# Schematic.net
KiCad netlist of a schematic drawn in EAGLE
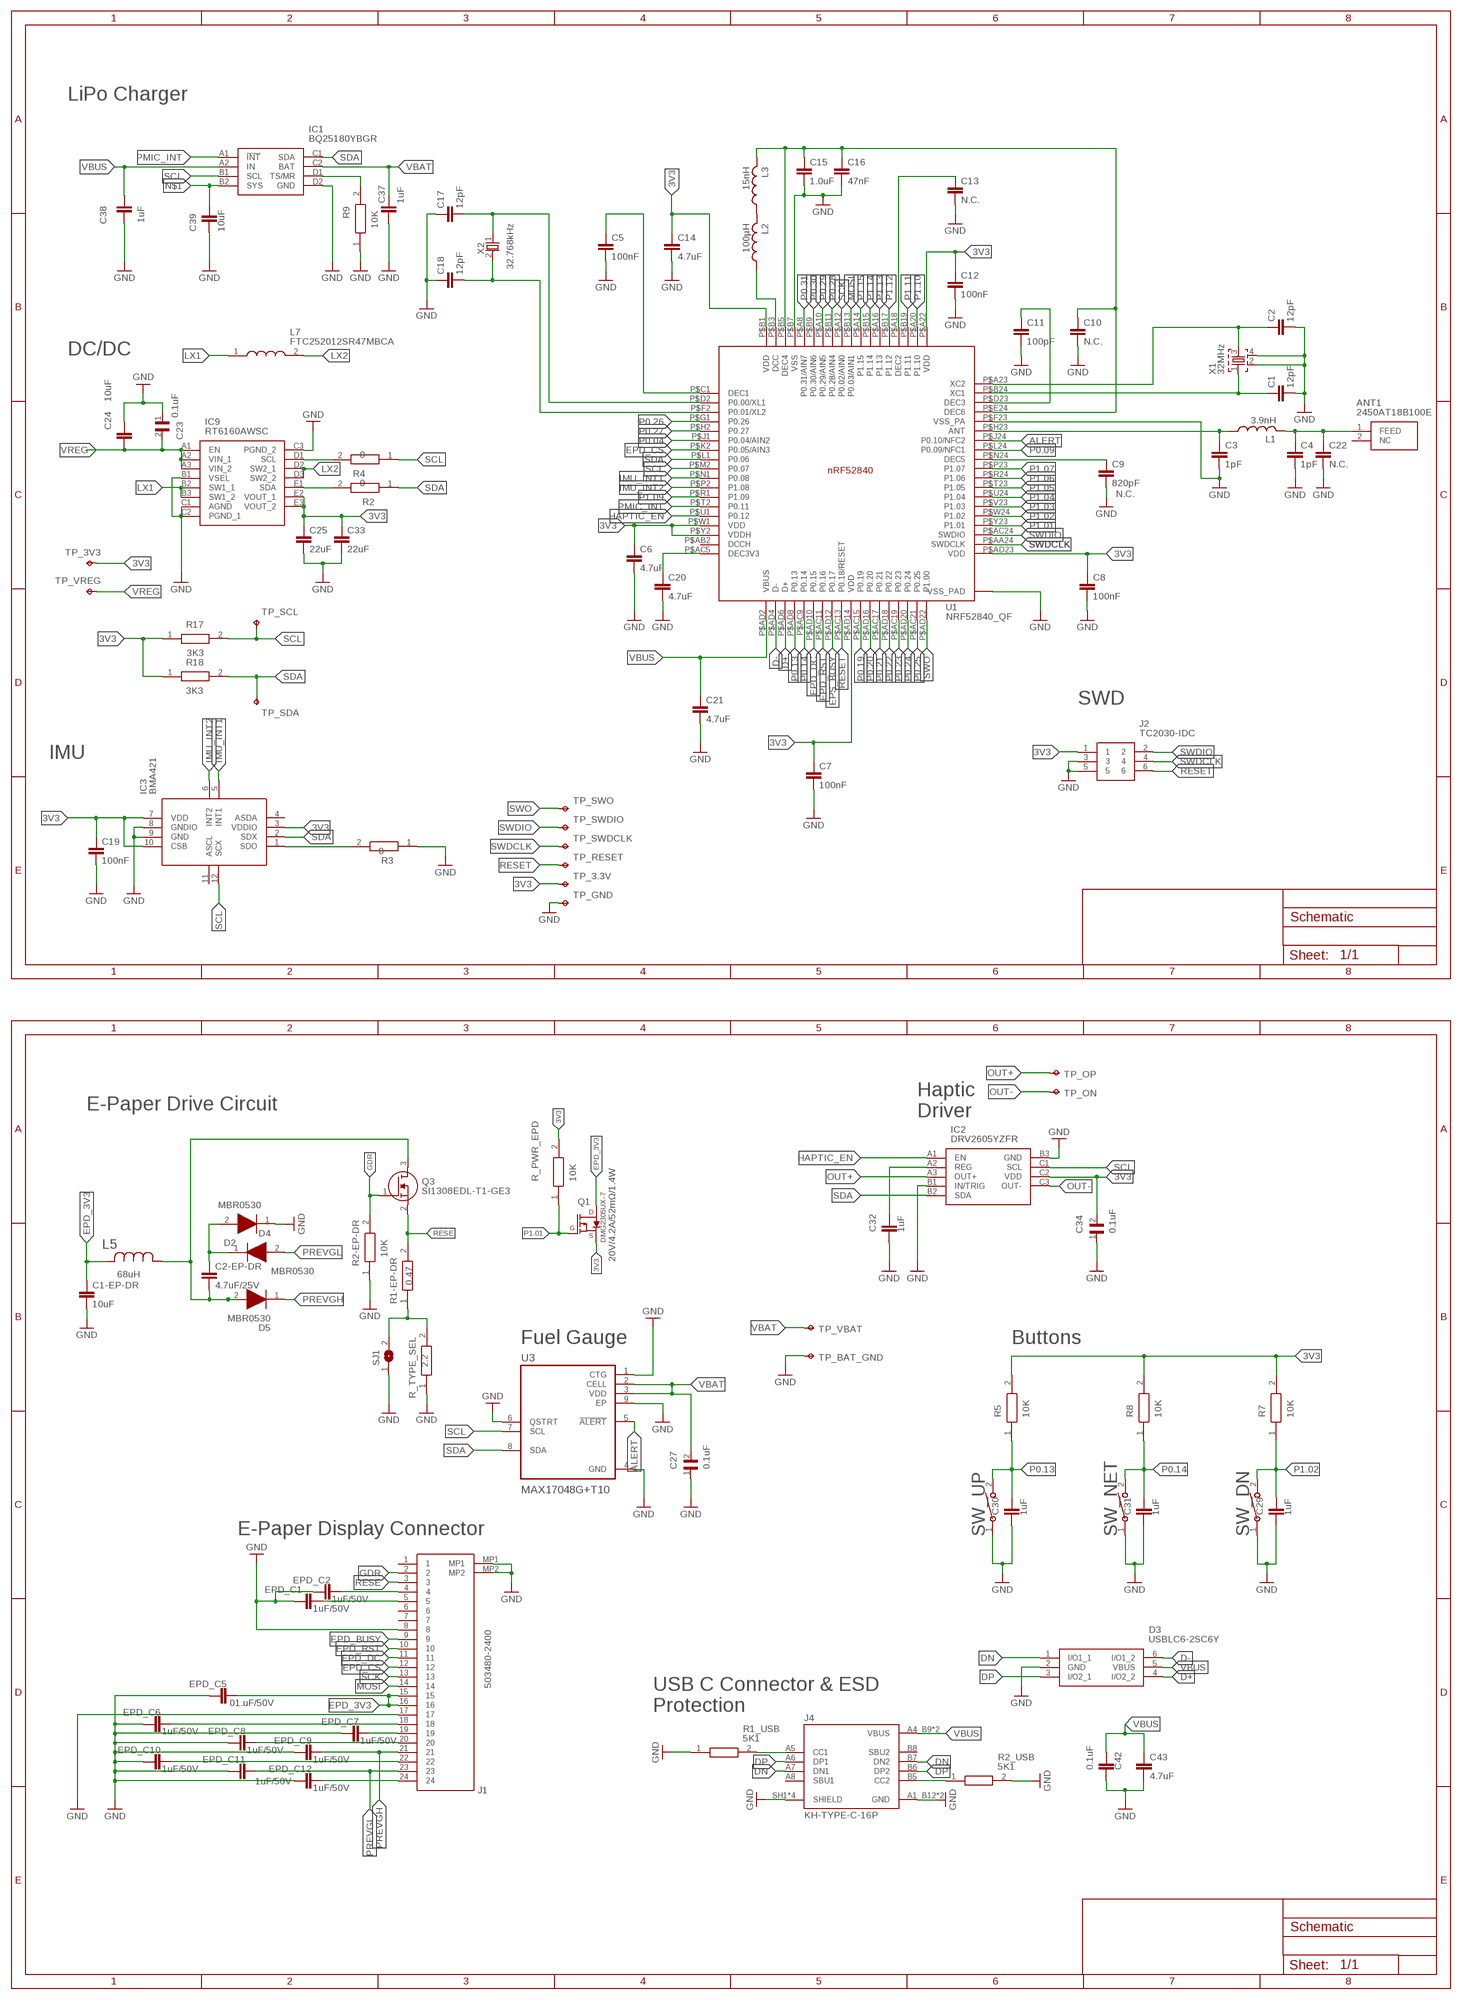
[diagram p0: schematic, sheet 1]

(export (version "E")
  (design (tool "Eeschema 10.0.6"))
  (components
    (comp (ref "ANT1")
      (value "2450AT18B100E")
      (footprint "eagle-import:2450AT18B100E_ANTC3216X140N")
      (fields (field (name "MOUSER_PART_NUMBER") "609-2450AT18B100E"))
      (libsource (lib "eagle-import") (part "2450AT18B100E_2450AT18B100E"))
    )
    (comp (ref "C1")
      (value "12pF")
      (footprint "eagle-import:NORDIC_NRF_3_RESC0201_L")
      (libsource (lib "eagle-import") (part "NORDIC_NRF_3_CAPACITOR_0201_L"))
    )
    (comp (ref "C1-EP-DR")
      (value "10uF")
      (footprint "eagle-import:NORDIC_NRF_3_RESC0201_L")
      (libsource (lib "eagle-import") (part "NORDIC_NRF_3_CAPACITOR_0201_L"))
    )
    (comp (ref "C2")
      (value "12pF")
      (footprint "eagle-import:NORDIC_NRF_3_RESC0201_L")
      (libsource (lib "eagle-import") (part "NORDIC_NRF_3_CAPACITOR_0201_L"))
    )
    (comp (ref "C2-EP-DR")
      (value "4.7uF/25V")
      (footprint "eagle-import:NORDIC_NRF_3_RESC0603_M")
      (libsource (lib "eagle-import") (part "NORDIC_NRF_3_CAPACITOR_0603_M"))
    )
    (comp (ref "C3")
      (value "1pF")
      (footprint "eagle-import:NORDIC_NRF_3_RESC0201_L")
      (libsource (lib "eagle-import") (part "NORDIC_NRF_3_CAPACITOR_0201_L"))
    )
    (comp (ref "C4")
      (value "1pF")
      (footprint "eagle-import:NORDIC_NRF_3_RESC0201_L")
      (libsource (lib "eagle-import") (part "NORDIC_NRF_3_CAPACITOR_0201_L"))
    )
    (comp (ref "C5")
      (value "100nF")
      (footprint "eagle-import:NORDIC_NRF_3_RESC0201_L")
      (libsource (lib "eagle-import") (part "NORDIC_NRF_3_CAPACITOR_0201_L"))
    )
    (comp (ref "C6")
      (value "4.7uF")
      (footprint "eagle-import:NORDIC_NRF_3_RESC0402_M")
      (libsource (lib "eagle-import") (part "NORDIC_NRF_3_CAPACITOR_0402_M"))
    )
    (comp (ref "C7")
      (value "100nF")
      (footprint "eagle-import:NORDIC_NRF_3_RESC0201_L")
      (libsource (lib "eagle-import") (part "NORDIC_NRF_3_CAPACITOR_0201_L"))
    )
    (comp (ref "C8")
      (value "100nF")
      (footprint "eagle-import:NORDIC_NRF_3_RESC0201_L")
      (libsource (lib "eagle-import") (part "NORDIC_NRF_3_CAPACITOR_0201_L"))
    )
    (comp (ref "C9")
      (value "820pF")
      (footprint "eagle-import:NORDIC_NRF_3_RESC0201_L")
      (fields (field (name "MAXTEMP") "N.C."))
      (libsource (lib "eagle-import") (part "NORDIC_NRF_3_CAPACITOR_0201_L"))
    )
    (comp (ref "C10")
      (value "N.C.")
      (footprint "eagle-import:NORDIC_NRF_3_RESC0201_L")
      (libsource (lib "eagle-import") (part "NORDIC_NRF_3_CAPACITOR_0201_L"))
    )
    (comp (ref "C11")
      (value "100pF")
      (footprint "eagle-import:NORDIC_NRF_3_RESC0201_L")
      (libsource (lib "eagle-import") (part "NORDIC_NRF_3_CAPACITOR_0201_L"))
    )
    (comp (ref "C12")
      (value "100nF")
      (footprint "eagle-import:NORDIC_NRF_3_RESC0201_L")
      (libsource (lib "eagle-import") (part "NORDIC_NRF_3_CAPACITOR_0201_L"))
    )
    (comp (ref "C13")
      (value "N.C.")
      (footprint "eagle-import:NORDIC_NRF_3_RESC0201_L")
      (libsource (lib "eagle-import") (part "NORDIC_NRF_3_CAPACITOR_0201_L"))
    )
    (comp (ref "C14")
      (value "4.7uF")
      (footprint "eagle-import:NORDIC_NRF_3_RESC0402_M")
      (libsource (lib "eagle-import") (part "NORDIC_NRF_3_CAPACITOR_0402_M"))
    )
    (comp (ref "C15")
      (value "1.0uF")
      (footprint "eagle-import:NORDIC_NRF_3_RESC0402_M")
      (libsource (lib "eagle-import") (part "NORDIC_NRF_3_CAPACITOR_0402_M"))
    )
    (comp (ref "C16")
      (value "47nF")
      (footprint "eagle-import:NORDIC_NRF_3_RESC0201_L")
      (libsource (lib "eagle-import") (part "NORDIC_NRF_3_CAPACITOR_0201_L"))
    )
    (comp (ref "C17")
      (value "12pF")
      (footprint "eagle-import:NORDIC_NRF_3_RESC0201_L")
      (libsource (lib "eagle-import") (part "NORDIC_NRF_3_CAPACITOR_0201_L"))
    )
    (comp (ref "C18")
      (value "12pF")
      (footprint "eagle-import:NORDIC_NRF_3_RESC0201_L")
      (libsource (lib "eagle-import") (part "NORDIC_NRF_3_CAPACITOR_0201_L"))
    )
    (comp (ref "C19")
      (value "100nF")
      (footprint "eagle-import:NORDIC_NRF_3_RESC0201_L")
      (libsource (lib "eagle-import") (part "NORDIC_NRF_3_CAPACITOR_0201_L"))
    )
    (comp (ref "C20")
      (value "4.7uF")
      (footprint "eagle-import:NORDIC_NRF_3_RESC0402_M")
      (libsource (lib "eagle-import") (part "NORDIC_NRF_3_CAPACITOR_0402_M"))
    )
    (comp (ref "C21")
      (value "4.7uF")
      (footprint "eagle-import:NORDIC_NRF_3_RESC0402_M")
      (libsource (lib "eagle-import") (part "NORDIC_NRF_3_CAPACITOR_0402_M"))
    )
    (comp (ref "C22")
      (value "N.C.")
      (footprint "eagle-import:NORDIC_NRF_3_RESC0201_L")
      (libsource (lib "eagle-import") (part "NORDIC_NRF_3_CAPACITOR_0201_L"))
    )
    (comp (ref "C23")
      (value "0.1uF")
      (footprint "eagle-import:GRM011R60J152KE01L_2_CAPC0201X13N")
      (fields (field (name "MF") "Murata") (field (name "MP") "GRM011R60J152KE01L"))
      (libsource (lib "eagle-import") (part "GRM011R60J152KE01L_2_GRM011R60J152KE01L"))
    )
    (comp (ref "C24")
      (value "10uF")
      (footprint "eagle-import:NORDIC_NRF_3_RESC0402_M")
      (libsource (lib "eagle-import") (part "NORDIC_NRF_3_CAPACITOR_0402_M"))
    )
    (comp (ref "C25")
      (value "22uF")
      (footprint "eagle-import:NORDIC_NRF_3_RESC0402_M")
      (libsource (lib "eagle-import") (part "NORDIC_NRF_3_CAPACITOR_0402_M"))
    )
    (comp (ref "C27")
      (value "0.1uF")
      (footprint "eagle-import:GRM011R60J152KE01L_2_CAPC0201X13N")
      (fields (field (name "MF") "Murata") (field (name "MP") "GRM011R60J152KE01L"))
      (libsource (lib "eagle-import") (part "GRM011R60J152KE01L_2_GRM011R60J152KE01L"))
    )
    (comp (ref "C29")
      (value "1uF")
      (footprint "eagle-import:NORDIC_NRF_3_RESC0402_M")
      (libsource (lib "eagle-import") (part "NORDIC_NRF_3_CAPACITOR_0402_M"))
    )
    (comp (ref "C30")
      (value "1uF")
      (footprint "eagle-import:NORDIC_NRF_3_RESC0402_M")
      (libsource (lib "eagle-import") (part "NORDIC_NRF_3_CAPACITOR_0402_M"))
    )
    (comp (ref "C31")
      (value "1uF")
      (footprint "eagle-import:NORDIC_NRF_3_RESC0402_M")
      (libsource (lib "eagle-import") (part "NORDIC_NRF_3_CAPACITOR_0402_M"))
    )
    (comp (ref "C32")
      (value "1uF")
      (footprint "eagle-import:NORDIC_NRF_3_RESC0402_M")
      (libsource (lib "eagle-import") (part "NORDIC_NRF_3_CAPACITOR_0402_M"))
    )
    (comp (ref "C33")
      (value "22uF")
      (footprint "eagle-import:NORDIC_NRF_3_RESC0402_M")
      (libsource (lib "eagle-import") (part "NORDIC_NRF_3_CAPACITOR_0402_M"))
    )
    (comp (ref "C34")
      (value "0.1uF")
      (footprint "eagle-import:GRM011R60J152KE01L_2_CAPC0201X13N")
      (fields (field (name "MF") "Murata") (field (name "MP") "GRM011R60J152KE01L"))
      (libsource (lib "eagle-import") (part "GRM011R60J152KE01L_2_GRM011R60J152KE01L"))
    )
    (comp (ref "C37")
      (value "1uF")
      (footprint "eagle-import:NORDIC_NRF_3_RESC0402_M")
      (libsource (lib "eagle-import") (part "NORDIC_NRF_3_CAPACITOR_0402_M"))
    )
    (comp (ref "C38")
      (value "1uF")
      (footprint "eagle-import:NORDIC_NRF_3_RESC0402_L")
      (libsource (lib "eagle-import") (part "NORDIC_NRF_3_CAPACITOR_0402_L"))
    )
    (comp (ref "C39")
      (value "10uF")
      (footprint "eagle-import:NORDIC_NRF_3_RESC0402_N")
      (libsource (lib "eagle-import") (part "NORDIC_NRF_3_CAPACITOR_0402_N"))
    )
    (comp (ref "C42")
      (value "0.1uF")
      (footprint "eagle-import:NORDIC_NRF_3_RESC0201_L")
      (libsource (lib "eagle-import") (part "NORDIC_NRF_3_CAPACITOR_0201_L"))
    )
    (comp (ref "C43")
      (value "4.7uF")
      (footprint "eagle-import:NORDIC_NRF_3_RESC0402_M")
      (libsource (lib "eagle-import") (part "NORDIC_NRF_3_CAPACITOR_0402_M"))
    )
    (comp (ref "D2")
      (value "MBR0530")
      (footprint "eagle-import:ESP32_C6_LIBRARY_5_SOD3716X135N")
      (fields (field (name "MF") "ON Semiconductor"))
      (libsource (lib "eagle-import") (part "ESP32_C6_LIBRARY_5_MBR0530"))
    )
    (comp (ref "D3")
      (value "USBLC6-2SC6Y")
      (footprint "eagle-import:ESP32_C6_LIBRARY_3_SOT95P280X145-6N")
      (fields (field (name "MF") "STMicroelectronics"))
      (libsource (lib "eagle-import") (part "ESP32_C6_LIBRARY_3_USBLC6-2SC6Y"))
    )
    (comp (ref "D4")
      (value "MBR0530")
      (footprint "eagle-import:ESP32_C6_LIBRARY_5_SOD3716X135N")
      (fields (field (name "MF") "ON Semiconductor"))
      (libsource (lib "eagle-import") (part "ESP32_C6_LIBRARY_5_MBR0530"))
    )
    (comp (ref "D5")
      (value "MBR0530")
      (footprint "eagle-import:ESP32_C6_LIBRARY_5_SOD3716X135N")
      (fields (field (name "MF") "ON Semiconductor"))
      (libsource (lib "eagle-import") (part "ESP32_C6_LIBRARY_5_MBR0530"))
    )
    (comp (ref "EPD_C1")
      (value "1uF/50V")
      (footprint "eagle-import:NORDIC_NRF_3_RESC0603_M")
      (libsource (lib "eagle-import") (part "NORDIC_NRF_3_CAPACITOR_0603_M"))
    )
    (comp (ref "EPD_C2")
      (value "1uF/50V")
      (footprint "eagle-import:NORDIC_NRF_3_RESC0603_M")
      (libsource (lib "eagle-import") (part "NORDIC_NRF_3_CAPACITOR_0603_M"))
    )
    (comp (ref "EPD_C5")
      (value "01.uF/50V")
      (footprint "eagle-import:NORDIC_NRF_3_RESC0603_M")
      (libsource (lib "eagle-import") (part "NORDIC_NRF_3_CAPACITOR_0603_M"))
    )
    (comp (ref "EPD_C6")
      (value "1uF/50V")
      (footprint "eagle-import:NORDIC_NRF_3_RESC0603_M")
      (libsource (lib "eagle-import") (part "NORDIC_NRF_3_CAPACITOR_0603_M"))
    )
    (comp (ref "EPD_C7")
      (value "1uF/50V")
      (footprint "eagle-import:NORDIC_NRF_3_RESC0603_M")
      (libsource (lib "eagle-import") (part "NORDIC_NRF_3_CAPACITOR_0603_M"))
    )
    (comp (ref "EPD_C8")
      (value "1uF/50V")
      (footprint "eagle-import:NORDIC_NRF_3_RESC0603_M")
      (libsource (lib "eagle-import") (part "NORDIC_NRF_3_CAPACITOR_0603_M"))
    )
    (comp (ref "EPD_C9")
      (value "1uF/50V")
      (footprint "eagle-import:NORDIC_NRF_3_RESC0603_M")
      (libsource (lib "eagle-import") (part "NORDIC_NRF_3_CAPACITOR_0603_M"))
    )
    (comp (ref "EPD_C10")
      (value "1uF/50V")
      (footprint "eagle-import:NORDIC_NRF_3_RESC0603_M")
      (libsource (lib "eagle-import") (part "NORDIC_NRF_3_CAPACITOR_0603_M"))
    )
    (comp (ref "EPD_C11")
      (value "1uF/50V")
      (footprint "eagle-import:NORDIC_NRF_3_RESC0603_M")
      (libsource (lib "eagle-import") (part "NORDIC_NRF_3_CAPACITOR_0603_M"))
    )
    (comp (ref "EPD_C12")
      (value "1uF/50V")
      (footprint "eagle-import:NORDIC_NRF_3_RESC0603_M")
      (libsource (lib "eagle-import") (part "NORDIC_NRF_3_CAPACITOR_0603_M"))
    )
    (comp (ref "IC1")
      (value "BQ25180YBGR")
      (footprint "eagle-import:BQ25180YBGR_BGA8C40P2X4_100X155X50")
      (fields (field (name "MOUSER_PART_NUMBER") "595-BQ25180YBGR"))
      (libsource (lib "eagle-import") (part "BQ25180YBGR_BQ25180YBGR"))
    )
    (comp (ref "IC2")
      (value "DRV2605YZFR")
      (footprint "eagle-import:DRV2605YZFR_BGA9C50P3X3_144X144X62")
      (libsource (lib "eagle-import") (part "DRV2605YZFR_DRV2605YZFR"))
    )
    (comp (ref "IC3")
      (value "BMA421")
      (footprint "eagle-import:BMA423_BMA423")
      (fields (field (name "ARROW_PART_NUMBER") "BMA423") (field (name "MOUSER_PART_NUMBER") "262-BMA423"))
      (libsource (lib "eagle-import") (part "BMA423_BMA423"))
    )
    (comp (ref "IC9")
      (value "RT6160AWSC")
      (footprint "eagle-import:RT6160AWSC_BGA15C40P3X5_140X230X60")
      (fields (field (name "MOUSER_PART_NUMBER") "835-RT6160AWSC"))
      (libsource (lib "eagle-import") (part "RT6160AWSC_RT6160AWSC"))
    )
    (comp (ref "J1")
      (value "503480-2400")
      (footprint "eagle-import:503480-2400_5034802400")
      (fields (field (name "MOUSER_PART_NUMBER") "538-503480-2400"))
      (libsource (lib "eagle-import") (part "503480-2400_503480-2400"))
    )
    (comp (ref "J2")
      (value "TC2030-IDC")
      (footprint "eagle-import:TC2030-IDC_TC2030IDC")
      (libsource (lib "eagle-import") (part "TC2030-IDC_TC2030-IDC"))
    )
    (comp (ref "J4")
      (value "KH-TYPE-C-16P")
      (footprint "eagle-import:KH-TYPE-C-16P_KINGHELM_KH-TYPE-C-16P")
      (fields (field (name "MF") "kinghelm"))
      (libsource (lib "eagle-import") (part "KH-TYPE-C-16P_KH-TYPE-C-16P"))
    )
    (comp (ref "L1")
      (value "3.9nH")
      (footprint "eagle-import:NORDIC_NRF_2_RESC0402_L")
      (libsource (lib "eagle-import") (part "NORDIC_NRF_2_INDUCTOR_0402_L"))
    )
    (comp (ref "L2")
      (value "100µH")
      (footprint "eagle-import:NORDIC_NRF_2_RESC0402_L")
      (libsource (lib "eagle-import") (part "NORDIC_NRF_2_INDUCTOR_0402_L"))
    )
    (comp (ref "L3")
      (value "15nH")
      (footprint "eagle-import:NORDIC_NRF_2_RESC0402_L")
      (libsource (lib "eagle-import") (part "NORDIC_NRF_2_INDUCTOR_0402_L"))
    )
    (comp (ref "L5")
      (value "68uH")
      (footprint "eagle-import:ESP32_C6_LIBRARY_2_IND_4828-WE-TPC_WRE")
      (fields
        (field (name "MANUFACTURER_PART_NUMBER") "744043680")
        (field (name "COPYRIGHT") "Copyright (C) 2024 Ultra Librarian. All rights reserved.")
      )
      (libsource (lib "eagle-import") (part "ESP32_C6_LIBRARY_2_744043680IND_4828-WE-TPC_WRE"))
    )
    (comp (ref "L7")
      (value "FTC252012SR47MBCA")
      (footprint "eagle-import:MLP2016SR47MT0S1_INDC2016X100N")
      (libsource (lib "eagle-import") (part "MLP2016SR47MT0S1_FTC252012SR47MBCA"))
    )
    (comp (ref "Q1")
      (value "20V/4.2A/52mΩ/1.4W")
      (footprint "eagle-import:ESP32_C6_LIBRARY_4_ESP32_C6_LIBRARY_4_ESP32_C6_LIBRARY_4_ESP32_C6_LIBRARY_4_ESP32_WROVER_SPARKFUN-DISCRETESEMI_SOT23-3")
      (libsource (lib "eagle-import") (part "ESP32_C6_LIBRARY_4_ESP32_WROVER_SPARKFUN-DISCRETESEMI_MOSFET_PCH-DMG2305UX-7"))
    )
    (comp (ref "Q3")
      (value "SI1308EDL-T1-GE3")
      (footprint "eagle-import:ESP32_C6_LIBRARY_6_SOT65P210X110-3N")
      (fields (field (name "MF") "Vishay Siliconix"))
      (libsource (lib "eagle-import") (part "ESP32_C6_LIBRARY_6_SI1308EDL-T1-GE3"))
    )
    (comp (ref "R1-EP-DR")
      (value "0.47")
      (footprint "eagle-import:ERA-1AEB3401C_0201")
      (libsource (lib "eagle-import") (part "ERA-1AEB3401C_CPF0201D7K68C1"))
    )
    (comp (ref "R1_USB")
      (value "5K1")
      (footprint "eagle-import:ERA-1AEB3401C_0201")
      (libsource (lib "eagle-import") (part "ERA-1AEB3401C_CPF0201D7K68C1"))
    )
    (comp (ref "R2")
      (value "0")
      (footprint "eagle-import:ERA-1AEB3401C_0201")
      (libsource (lib "eagle-import") (part "ERA-1AEB3401C_CPF0201D7K68C1"))
    )
    (comp (ref "R2-EP-DR")
      (value "10K")
      (footprint "eagle-import:ERA-1AEB3401C_0201")
      (libsource (lib "eagle-import") (part "ERA-1AEB3401C_CPF0201D7K68C1"))
    )
    (comp (ref "R2_USB")
      (value "5K1")
      (footprint "eagle-import:ERA-1AEB3401C_0201")
      (libsource (lib "eagle-import") (part "ERA-1AEB3401C_CPF0201D7K68C1"))
    )
    (comp (ref "R3")
      (value "0")
      (footprint "eagle-import:ERA-1AEB3401C_0201")
      (libsource (lib "eagle-import") (part "ERA-1AEB3401C_CPF0201D7K68C1"))
    )
    (comp (ref "R4")
      (value "0")
      (footprint "eagle-import:ERA-1AEB3401C_0201")
      (libsource (lib "eagle-import") (part "ERA-1AEB3401C_CPF0201D7K68C1"))
    )
    (comp (ref "R5")
      (value "10K")
      (footprint "eagle-import:ERA-1AEB3401C_0201")
      (libsource (lib "eagle-import") (part "ERA-1AEB3401C_CPF0201D7K68C1"))
    )
    (comp (ref "R7")
      (value "10K")
      (footprint "eagle-import:ERA-1AEB3401C_0201")
      (libsource (lib "eagle-import") (part "ERA-1AEB3401C_CPF0201D7K68C1"))
    )
    (comp (ref "R8")
      (value "10K")
      (footprint "eagle-import:ERA-1AEB3401C_0201")
      (libsource (lib "eagle-import") (part "ERA-1AEB3401C_CPF0201D7K68C1"))
    )
    (comp (ref "R9")
      (value "10K")
      (footprint "eagle-import:ERA-1AEB3401C_0201")
      (libsource (lib "eagle-import") (part "ERA-1AEB3401C_CPF0201D7K68C1"))
    )
    (comp (ref "R17")
      (value "3K3")
      (footprint "eagle-import:ERA-1AEB3401C_0201")
      (libsource (lib "eagle-import") (part "ERA-1AEB3401C_CPF0201D7K68C1"))
    )
    (comp (ref "R18")
      (value "3K3")
      (footprint "eagle-import:ERA-1AEB3401C_0201")
      (libsource (lib "eagle-import") (part "ERA-1AEB3401C_CPF0201D7K68C1"))
    )
    (comp (ref "R_PWR_EPD")
      (value "10K")
      (footprint "eagle-import:ERA-1AEB3401C_0201")
      (libsource (lib "eagle-import") (part "ERA-1AEB3401C_CPF0201D7K68C1"))
    )
    (comp (ref "R_TYPE_SEL")
      (value "2.2")
      (footprint "eagle-import:ERA-1AEB3401C_0201")
      (libsource (lib "eagle-import") (part "ERA-1AEB3401C_CPF0201D7K68C1"))
    )
    (comp (ref "SJ1")
      (value "ESP32_C6_LIBRARY_7_JUMPER_SJ")
      (footprint "eagle-import:ESP32_C6_LIBRARY_7_JUMPER_SJ")
      (libsource (lib "eagle-import") (part "ESP32_C6_LIBRARY_7_JUMPER_SJ"))
    )
    (comp (ref "SW_DN")
      (value "2025-10-22_07-23-44_LIBRARY_EVP-AKE31ASW_EVP-AKE31A_PAN")
      (footprint "eagle-import:2025-10-22_07-23-44_LIBRARY_SW_EVP-AKE31A_PAN")
      (fields
        (field (name "MANUFACTURER_PART_NUMBER") "EVP-AKE31A")
        (field (name "COPYRIGHT") "Copyright (C) 2025 Ultra Librarian. All rights reserved.")
      )
      (libsource (lib "eagle-import") (part "2025-10-22_07-23-44_LIBRARY_EVP-AKE31ASW_EVP-AKE31A_PAN"))
    )
    (comp (ref "SW_NET")
      (value "2025-10-22_07-23-44_LIBRARY_EVP-AKE31ASW_EVP-AKE31A_PAN")
      (footprint "eagle-import:2025-10-22_07-23-44_LIBRARY_SW_EVP-AKE31A_PAN")
      (fields
        (field (name "MANUFACTURER_PART_NUMBER") "EVP-AKE31A")
        (field (name "COPYRIGHT") "Copyright (C) 2025 Ultra Librarian. All rights reserved.")
      )
      (libsource (lib "eagle-import") (part "2025-10-22_07-23-44_LIBRARY_EVP-AKE31ASW_EVP-AKE31A_PAN"))
    )
    (comp (ref "SW_UP")
      (value "2025-10-22_07-23-44_LIBRARY_EVP-AKE31ASW_EVP-AKE31A_PAN")
      (footprint "eagle-import:2025-10-22_07-23-44_LIBRARY_SW_EVP-AKE31A_PAN")
      (fields
        (field (name "MANUFACTURER_PART_NUMBER") "EVP-AKE31A")
        (field (name "COPYRIGHT") "Copyright (C) 2025 Ultra Librarian. All rights reserved.")
      )
      (libsource (lib "eagle-import") (part "2025-10-22_07-23-44_LIBRARY_EVP-AKE31ASW_EVP-AKE31A_PAN"))
    )
    (comp (ref "TP_3.3V")
      (value "HECTOR_WATCH_1_TPTP20R")
      (footprint "eagle-import:HECTOR_WATCH_1_TP20R")
      (libsource (lib "eagle-import") (part "HECTOR_WATCH_1_TPTP20R"))
    )
    (comp (ref "TP_3V3")
      (value "HECTOR_WATCH_1_TPTP20R")
      (footprint "eagle-import:HECTOR_WATCH_1_TP20R")
      (libsource (lib "eagle-import") (part "HECTOR_WATCH_1_TPTP20R"))
    )
    (comp (ref "TP_BAT_GND")
      (value "HECTOR_WATCH_1_TPTP20R")
      (footprint "eagle-import:HECTOR_WATCH_1_TP20R")
      (libsource (lib "eagle-import") (part "HECTOR_WATCH_1_TPTP20R"))
    )
    (comp (ref "TP_GND")
      (value "HECTOR_WATCH_1_TPTP20R")
      (footprint "eagle-import:HECTOR_WATCH_1_TP20R")
      (libsource (lib "eagle-import") (part "HECTOR_WATCH_1_TPTP20R"))
    )
    (comp (ref "TP_ON")
      (value "HECTOR_WATCH_1_TPTP20R")
      (footprint "eagle-import:HECTOR_WATCH_1_TP20R")
      (libsource (lib "eagle-import") (part "HECTOR_WATCH_1_TPTP20R"))
    )
    (comp (ref "TP_OP")
      (value "HECTOR_WATCH_1_TPTP20R")
      (footprint "eagle-import:HECTOR_WATCH_1_TP20R")
      (libsource (lib "eagle-import") (part "HECTOR_WATCH_1_TPTP20R"))
    )
    (comp (ref "TP_RESET")
      (value "HECTOR_WATCH_1_TPTP20R")
      (footprint "eagle-import:HECTOR_WATCH_1_TP20R")
      (libsource (lib "eagle-import") (part "HECTOR_WATCH_1_TPTP20R"))
    )
    (comp (ref "TP_SCL")
      (value "HECTOR_WATCH_1_TPTP20R")
      (footprint "eagle-import:HECTOR_WATCH_1_TP20R")
      (libsource (lib "eagle-import") (part "HECTOR_WATCH_1_TPTP20R"))
    )
    (comp (ref "TP_SDA")
      (value "HECTOR_WATCH_1_TPTP20R")
      (footprint "eagle-import:HECTOR_WATCH_1_TP20R")
      (libsource (lib "eagle-import") (part "HECTOR_WATCH_1_TPTP20R"))
    )
    (comp (ref "TP_SWDCLK")
      (value "HECTOR_WATCH_1_TPTP20R")
      (footprint "eagle-import:HECTOR_WATCH_1_TP20R")
      (libsource (lib "eagle-import") (part "HECTOR_WATCH_1_TPTP20R"))
    )
    (comp (ref "TP_SWDIO")
      (value "HECTOR_WATCH_1_TPTP20R")
      (footprint "eagle-import:HECTOR_WATCH_1_TP20R")
      (libsource (lib "eagle-import") (part "HECTOR_WATCH_1_TPTP20R"))
    )
    (comp (ref "TP_SWO")
      (value "HECTOR_WATCH_1_TPTP20R")
      (footprint "eagle-import:HECTOR_WATCH_1_TP20R")
      (libsource (lib "eagle-import") (part "HECTOR_WATCH_1_TPTP20R"))
    )
    (comp (ref "TP_VBAT")
      (value "HECTOR_WATCH_1_TPTP20R")
      (footprint "eagle-import:HECTOR_WATCH_1_TP20R")
      (libsource (lib "eagle-import") (part "HECTOR_WATCH_1_TPTP20R"))
    )
    (comp (ref "TP_VREG")
      (value "HECTOR_WATCH_1_TPTP20R")
      (footprint "eagle-import:HECTOR_WATCH_1_TP20R")
      (libsource (lib "eagle-import") (part "HECTOR_WATCH_1_TPTP20R"))
    )
    (comp (ref "U1")
      (value "NRF52840_QF")
      (footprint "eagle-import:NORDIC_NRF_4_AQFN50P700X700X85_HS-74N")
      (libsource (lib "eagle-import") (part "NORDIC_NRF_4_NRF52840_QF"))
    )
    (comp (ref "U3")
      (value "MAX17048G+T10")
      (footprint "eagle-import:ESP32_C6_LIBRARY_SON50P200X200X80-9N")
      (fields (field (name "MF") "Analog Devices"))
      (libsource (lib "eagle-import") (part "ESP32_C6_LIBRARY_MAX17048G+T10"))
    )
    (comp (ref "X1")
      (value "32MHz")
      (footprint "eagle-import:NORDIC_NRF_BT-XTAL_2016_N")
      (libsource (lib "eagle-import") (part "NORDIC_NRF_XTAL_32MHZ"))
    )
    (comp (ref "X2")
      (value "32.768kHz")
      (footprint "eagle-import:NORDIC_NRF_1_XTAL_3215_N")
      (libsource (lib "eagle-import") (part "NORDIC_NRF_1_XTAL_32KHZ"))
    )
  )
  (nets
    (net (code "1") (name "3V3") (class "Default")
      (node (ref "C12") (pin "1") (pinfunction "1_1") (pintype "passive"))
      (node (ref "C14") (pin "1") (pinfunction "1_1") (pintype "passive"))
      (node (ref "C19") (pin "1") (pinfunction "1_1") (pintype "passive"))
      (node (ref "C25") (pin "1") (pinfunction "1_1") (pintype "passive"))
      (node (ref "C33") (pin "1") (pinfunction "1_1") (pintype "passive"))
      (node (ref "C34") (pin "2") (pinfunction "2_2") (pintype "passive"))
      (node (ref "C6") (pin "1") (pinfunction "1_1") (pintype "passive"))
      (node (ref "C7") (pin "1") (pinfunction "1_1") (pintype "passive"))
      (node (ref "C8") (pin "1") (pinfunction "1_1") (pintype "passive"))
      (node (ref "IC2") (pin "C2") (pinfunction "VDD_C2") (pintype "bidirectional"))
      (node (ref "IC3") (pin "10") (pinfunction "CSB_10") (pintype "bidirectional"))
      (node (ref "IC3") (pin "3") (pinfunction "VDDIO_3") (pintype "bidirectional"))
      (node (ref "IC3") (pin "7") (pinfunction "VDD_7") (pintype "bidirectional"))
      (node (ref "IC9") (pin "E2") (pinfunction "VOUT_1_E2") (pintype "bidirectional"))
      (node (ref "IC9") (pin "E3") (pinfunction "VOUT_2_E3") (pintype "bidirectional"))
      (node (ref "J2") (pin "1") (pinfunction "1_1") (pintype "bidirectional"))
      (node (ref "Q1") (pin "2") (pinfunction "S_2") (pintype "bidirectional"))
      (node (ref "R17") (pin "1") (pinfunction "1_1") (pintype "bidirectional"))
      (node (ref "R18") (pin "1") (pinfunction "1_1") (pintype "bidirectional"))
      (node (ref "R5") (pin "2") (pinfunction "2_2") (pintype "bidirectional"))
      (node (ref "R7") (pin "2") (pinfunction "2_2") (pintype "bidirectional"))
      (node (ref "R8") (pin "2") (pinfunction "2_2") (pintype "bidirectional"))
      (node (ref "R_PWR_EPD") (pin "2") (pinfunction "2_2") (pintype "bidirectional"))
      (node (ref "TP_3.3V") (pin "TP") (pinfunction "TP_TP") (pintype "input"))
      (node (ref "TP_3V3") (pin "TP") (pinfunction "TP_TP") (pintype "input"))
      (node (ref "U1") (pin "P$A22") (pinfunction "VDD_P$A22") (pintype "power_in"))
      (node (ref "U1") (pin "P$AD14") (pinfunction "VDD_P$AD14") (pintype "power_in"))
      (node (ref "U1") (pin "P$AD23") (pinfunction "VDD_P$AD23") (pintype "power_in"))
      (node (ref "U1") (pin "P$B1") (pinfunction "VDD_P$B1") (pintype "power_in"))
      (node (ref "U1") (pin "P$W1") (pinfunction "VDD_P$W1") (pintype "power_in"))
      (node (ref "U1") (pin "P$Y2") (pinfunction "VDDH_P$Y2") (pintype "power_in"))
    )
    (net (code "2") (name "ALERT") (class "Default")
      (node (ref "U1") (pin "P$J24") (pinfunction "P0.10/NFC2_P$J24") (pintype "bidirectional"))
      (node (ref "U3") (pin "5") (pinfunction "~{ALERT}_5") (pintype "output"))
    )
    (net (code "3") (name "D+") (class "Default")
      (node (ref "D3") (pin "4") (pinfunction "I/O2_2_4") (pintype "bidirectional"))
      (node (ref "U1") (pin "P$AD6") (pinfunction "D+_P$AD6") (pintype "bidirectional"))
    )
    (net (code "4") (name "D-") (class "Default")
      (node (ref "D3") (pin "6") (pinfunction "I/O1_2_6") (pintype "bidirectional"))
      (node (ref "U1") (pin "P$AD4") (pinfunction "D-_P$AD4") (pintype "bidirectional"))
    )
    (net (code "5") (name "DN") (class "Default")
      (node (ref "D3") (pin "1") (pinfunction "I/O1_1_1") (pintype "bidirectional"))
      (node (ref "J4") (pin "A7") (pinfunction "DN1_A7") (pintype "bidirectional"))
      (node (ref "J4") (pin "B7") (pinfunction "DN2_B7") (pintype "bidirectional"))
    )
    (net (code "6") (name "DP") (class "Default")
      (node (ref "D3") (pin "3") (pinfunction "I/O2_1_3") (pintype "bidirectional"))
      (node (ref "J4") (pin "A6") (pinfunction "DP1_A6") (pintype "bidirectional"))
      (node (ref "J4") (pin "B6") (pinfunction "DP2_B6") (pintype "bidirectional"))
    )
    (net (code "7") (name "EPD_3V3") (class "Default")
      (node (ref "C1-EP-DR") (pin "1") (pinfunction "1_1") (pintype "passive"))
      (node (ref "EPD_C5") (pin "2") (pinfunction "2_2") (pintype "passive"))
      (node (ref "J1") (pin "15") (pinfunction "15_15") (pintype "bidirectional"))
      (node (ref "J1") (pin "16") (pinfunction "16_16") (pintype "bidirectional"))
      (node (ref "L5") (pin "2") (pinfunction "2_2") (pintype "passive"))
      (node (ref "Q1") (pin "3") (pinfunction "D_3") (pintype "bidirectional"))
    )
    (net (code "8") (name "EPD_BUSY") (class "Default")
      (node (ref "J1") (pin "9") (pinfunction "9_9") (pintype "bidirectional"))
    )
    (net (code "9") (name "EPD_CS") (class "Default")
      (node (ref "J1") (pin "12") (pinfunction "12_12") (pintype "bidirectional"))
      (node (ref "U1") (pin "P$K2") (pinfunction "P0.05/AIN3_P$K2") (pintype "bidirectional"))
    )
    (net (code "10") (name "EPD_DC") (class "Default")
      (node (ref "J1") (pin "11") (pinfunction "11_11") (pintype "bidirectional"))
      (node (ref "U1") (pin "P$AD10") (pinfunction "P0.15_P$AD10") (pintype "bidirectional"))
    )
    (net (code "11") (name "EPD_RST") (class "Default")
      (node (ref "J1") (pin "10") (pinfunction "10_10") (pintype "bidirectional"))
      (node (ref "U1") (pin "P$AC11") (pinfunction "P0.16_P$AC11") (pintype "bidirectional"))
    )
    (net (code "12") (name "EPS_BUSY") (class "Default")
      (node (ref "U1") (pin "P$AD12") (pinfunction "P0.17_P$AD12") (pintype "bidirectional"))
    )
    (net (code "13") (name "GDR") (class "Default")
      (node (ref "J1") (pin "2") (pinfunction "2_2") (pintype "bidirectional"))
      (node (ref "Q3") (pin "1") (pinfunction "G_1") (pintype "bidirectional"))
      (node (ref "R2-EP-DR") (pin "2") (pinfunction "2_2") (pintype "bidirectional"))
    )
    (net (code "14") (name "GND") (class "Default")
      (node (ref "C1") (pin "2") (pinfunction "2_2") (pintype "passive"))
      (node (ref "C1-EP-DR") (pin "2") (pinfunction "2_2") (pintype "passive"))
      (node (ref "C10") (pin "2") (pinfunction "2_2") (pintype "passive"))
      (node (ref "C11") (pin "2") (pinfunction "2_2") (pintype "passive"))
      (node (ref "C12") (pin "2") (pinfunction "2_2") (pintype "passive"))
      (node (ref "C13") (pin "2") (pinfunction "2_2") (pintype "passive"))
      (node (ref "C14") (pin "2") (pinfunction "2_2") (pintype "passive"))
      (node (ref "C15") (pin "2") (pinfunction "2_2") (pintype "passive"))
      (node (ref "C16") (pin "2") (pinfunction "2_2") (pintype "passive"))
      (node (ref "C17") (pin "1") (pinfunction "1_1") (pintype "passive"))
      (node (ref "C18") (pin "1") (pinfunction "1_1") (pintype "passive"))
      (node (ref "C19") (pin "2") (pinfunction "2_2") (pintype "passive"))
      (node (ref "C2") (pin "2") (pinfunction "2_2") (pintype "passive"))
      (node (ref "C20") (pin "2") (pinfunction "2_2") (pintype "passive"))
      (node (ref "C21") (pin "2") (pinfunction "2_2") (pintype "passive"))
      (node (ref "C22") (pin "2") (pinfunction "2_2") (pintype "passive"))
      (node (ref "C23") (pin "1") (pinfunction "1_1") (pintype "passive"))
      (node (ref "C24") (pin "1") (pinfunction "1_1") (pintype "passive"))
      (node (ref "C25") (pin "2") (pinfunction "2_2") (pintype "passive"))
      (node (ref "C27") (pin "1") (pinfunction "1_1") (pintype "passive"))
      (node (ref "C29") (pin "2") (pinfunction "2_2") (pintype "passive"))
      (node (ref "C3") (pin "2") (pinfunction "2_2") (pintype "passive"))
      (node (ref "C30") (pin "2") (pinfunction "2_2") (pintype "passive"))
      (node (ref "C31") (pin "2") (pinfunction "2_2") (pintype "passive"))
      (node (ref "C32") (pin "2") (pinfunction "2_2") (pintype "passive"))
      (node (ref "C33") (pin "2") (pinfunction "2_2") (pintype "passive"))
      (node (ref "C34") (pin "1") (pinfunction "1_1") (pintype "passive"))
      (node (ref "C37") (pin "2") (pinfunction "2_2") (pintype "passive"))
      (node (ref "C38") (pin "1") (pinfunction "1_1") (pintype "passive"))
      (node (ref "C39") (pin "2") (pinfunction "2_2") (pintype "passive"))
      (node (ref "C4") (pin "2") (pinfunction "2_2") (pintype "passive"))
      (node (ref "C42") (pin "2") (pinfunction "2_2") (pintype "passive"))
      (node (ref "C43") (pin "2") (pinfunction "2_2") (pintype "passive"))
      (node (ref "C5") (pin "2") (pinfunction "2_2") (pintype "passive"))
      (node (ref "C6") (pin "2") (pinfunction "2_2") (pintype "passive"))
      (node (ref "C7") (pin "2") (pinfunction "2_2") (pintype "passive"))
      (node (ref "C8") (pin "2") (pinfunction "2_2") (pintype "passive"))
      (node (ref "C9") (pin "2") (pinfunction "2_2") (pintype "passive"))
      (node (ref "D3") (pin "2") (pinfunction "GND_2") (pintype "bidirectional"))
      (node (ref "D4") (pin "1") (pinfunction "K_1") (pintype "bidirectional"))
      (node (ref "EPD_C1") (pin "1") (pinfunction "1_1") (pintype "passive"))
      (node (ref "EPD_C10") (pin "1") (pinfunction "1_1") (pintype "passive"))
      (node (ref "EPD_C11") (pin "1") (pinfunction "1_1") (pintype "passive"))
      (node (ref "EPD_C12") (pin "1") (pinfunction "1_1") (pintype "passive"))
      (node (ref "EPD_C2") (pin "1") (pinfunction "1_1") (pintype "passive"))
      (node (ref "EPD_C5") (pin "1") (pinfunction "1_1") (pintype "passive"))
      (node (ref "EPD_C6") (pin "1") (pinfunction "1_1") (pintype "passive"))
      (node (ref "EPD_C7") (pin "1") (pinfunction "1_1") (pintype "passive"))
      (node (ref "EPD_C8") (pin "1") (pinfunction "1_1") (pintype "passive"))
      (node (ref "EPD_C9") (pin "1") (pinfunction "1_1") (pintype "passive"))
      (node (ref "IC1") (pin "D2") (pinfunction "GND_D2") (pintype "bidirectional"))
      (node (ref "IC2") (pin "B1") (pinfunction "IN/TRIG_B1") (pintype "bidirectional"))
      (node (ref "IC2") (pin "B3") (pinfunction "GND_B3") (pintype "bidirectional"))
      (node (ref "IC3") (pin "8") (pinfunction "GNDIO_8") (pintype "bidirectional"))
      (node (ref "IC3") (pin "9") (pinfunction "GND_9") (pintype "bidirectional"))
      (node (ref "IC9") (pin "B1") (pinfunction "VSEL_B1") (pintype "bidirectional"))
      (node (ref "IC9") (pin "C1") (pinfunction "AGND_C1") (pintype "bidirectional"))
      (node (ref "IC9") (pin "C2") (pinfunction "PGND_1_C2") (pintype "bidirectional"))
      (node (ref "IC9") (pin "C3") (pinfunction "PGND_2_C3") (pintype "bidirectional"))
      (node (ref "J1") (pin "17") (pinfunction "17_17") (pintype "bidirectional"))
      (node (ref "J1") (pin "8") (pinfunction "8_8") (pintype "bidirectional"))
      (node (ref "J1") (pin "MP1") (pinfunction "MP1_MP1") (pintype "bidirectional"))
      (node (ref "J1") (pin "MP2") (pinfunction "MP2_MP2") (pintype "bidirectional"))
      (node (ref "J2") (pin "3") (pinfunction "3_3") (pintype "bidirectional"))
      (node (ref "J2") (pin "5") (pinfunction "5_5") (pintype "bidirectional"))
      (node (ref "J4") (pin "A12_B1") (pinfunction "GND_A12_B1") (pintype "power_in"))
      (node (ref "J4") (pin "A1_B12") (pinfunction "GND_A1_B12") (pintype "power_in"))
      (node (ref "J4") (pin "SH1") (pinfunction "SHIELD_SH1") (pintype "passive"))
      (node (ref "J4") (pin "SH2") (pinfunction "SHIELD_SH2") (pintype "passive"))
      (node (ref "J4") (pin "SH3") (pinfunction "SHIELD_SH3") (pintype "passive"))
      (node (ref "J4") (pin "SH4") (pinfunction "SHIELD_SH4") (pintype "passive"))
      (node (ref "R1_USB") (pin "1") (pinfunction "1_1") (pintype "bidirectional"))
      (node (ref "R2-EP-DR") (pin "1") (pinfunction "1_1") (pintype "bidirectional"))
      (node (ref "R2_USB") (pin "2") (pinfunction "2_2") (pintype "bidirectional"))
      (node (ref "R3") (pin "1") (pinfunction "1_1") (pintype "bidirectional"))
      (node (ref "R9") (pin "1") (pinfunction "1_1") (pintype "bidirectional"))
      (node (ref "R_TYPE_SEL") (pin "1") (pinfunction "1_1") (pintype "bidirectional"))
      (node (ref "SJ1") (pin "1") (pinfunction "1_1") (pintype "passive"))
      (node (ref "SW_DN") (pin "1") (pinfunction "1_1") (pintype "passive"))
      (node (ref "SW_NET") (pin "1") (pinfunction "1_1") (pintype "passive"))
      (node (ref "SW_UP") (pin "1") (pinfunction "1_1") (pintype "passive"))
      (node (ref "TP_BAT_GND") (pin "TP") (pinfunction "TP_TP") (pintype "input"))
      (node (ref "TP_GND") (pin "TP") (pinfunction "TP_TP") (pintype "input"))
      (node (ref "U1") (pin "P$74") (pinfunction "VSS_PAD_P$74") (pintype "bidirectional"))
      (node (ref "U1") (pin "P$75") (pinfunction "VSS_PAD_P$75") (pintype "bidirectional"))
      (node (ref "U1") (pin "P$76") (pinfunction "VSS_PAD_P$76") (pintype "bidirectional"))
      (node (ref "U1") (pin "P$77") (pinfunction "VSS_PAD_P$77") (pintype "bidirectional"))
      (node (ref "U1") (pin "P$78") (pinfunction "VSS_PAD_P$78") (pintype "bidirectional"))
      (node (ref "U1") (pin "P$79") (pinfunction "VSS_PAD_P$79") (pintype "bidirectional"))
      (node (ref "U1") (pin "P$80") (pinfunction "VSS_PAD_P$80") (pintype "bidirectional"))
      (node (ref "U1") (pin "P$81") (pinfunction "VSS_PAD_P$81") (pintype "bidirectional"))
      (node (ref "U1") (pin "P$82") (pinfunction "VSS_PAD_P$82") (pintype "bidirectional"))
      (node (ref "U1") (pin "P$83") (pinfunction "VSS_PAD_P$83") (pintype "bidirectional"))
      (node (ref "U1") (pin "P$84") (pinfunction "VSS_PAD_P$84") (pintype "bidirectional"))
      (node (ref "U1") (pin "P$85") (pinfunction "VSS_PAD_P$85") (pintype "bidirectional"))
      (node (ref "U1") (pin "P$86") (pinfunction "VSS_PAD_P$86") (pintype "bidirectional"))
      (node (ref "U1") (pin "P$87") (pinfunction "VSS_PAD_P$87") (pintype "bidirectional"))
      (node (ref "U1") (pin "P$88") (pinfunction "VSS_PAD_P$88") (pintype "bidirectional"))
      (node (ref "U1") (pin "P$89") (pinfunction "VSS_PAD_P$89") (pintype "bidirectional"))
      (node (ref "U1") (pin "P$90") (pinfunction "VSS_PAD_P$90") (pintype "bidirectional"))
      (node (ref "U1") (pin "P$B7") (pinfunction "VSS_P$B7") (pintype "power_in"))
      (node (ref "U1") (pin "P$F23") (pinfunction "VSS_PA_P$F23") (pintype "bidirectional"))
      (node (ref "U3") (pin "1") (pinfunction "CTG_1") (pintype "power_in"))
      (node (ref "U3") (pin "4") (pinfunction "GND_4") (pintype "power_in"))
      (node (ref "U3") (pin "6") (pinfunction "QSTRT_6") (pintype "input"))
      (node (ref "U3") (pin "9") (pinfunction "EP_9") (pintype "power_in"))
      (node (ref "X1") (pin "2") (pinfunction "2_2") (pintype "passive"))
      (node (ref "X1") (pin "4") (pinfunction "4_4") (pintype "passive"))
    )
    (net (code "15") (name "HAPTIC_EN") (class "Default")
      (node (ref "IC2") (pin "A1") (pinfunction "EN_A1") (pintype "bidirectional"))
      (node (ref "U1") (pin "P$U1") (pinfunction "P0.12_P$U1") (pintype "bidirectional"))
    )
    (net (code "16") (name "IMU_INT1") (class "Default")
      (node (ref "IC3") (pin "5") (pinfunction "INT1_5") (pintype "bidirectional"))
      (node (ref "U1") (pin "P$N1") (pinfunction "P0.08_P$N1") (pintype "bidirectional"))
    )
    (net (code "17") (name "IMU_INT2") (class "Default")
      (node (ref "IC3") (pin "6") (pinfunction "INT2_6") (pintype "bidirectional"))
      (node (ref "U1") (pin "P$P2") (pinfunction "P1.08_P$P2") (pintype "bidirectional"))
    )
    (net (code "18") (name "LX1") (class "Default")
      (node (ref "IC9") (pin "B2") (pinfunction "SW1_1_B2") (pintype "bidirectional"))
      (node (ref "IC9") (pin "B3") (pinfunction "SW1_2_B3") (pintype "bidirectional"))
      (node (ref "L7") (pin "1") (pinfunction "1_1") (pintype "bidirectional"))
    )
    (net (code "19") (name "LX2") (class "Default")
      (node (ref "IC9") (pin "D2") (pinfunction "SW2_1_D2") (pintype "bidirectional"))
      (node (ref "IC9") (pin "D3") (pinfunction "SW2_2_D3") (pintype "bidirectional"))
      (node (ref "L7") (pin "2") (pinfunction "2_2") (pintype "bidirectional"))
    )
    (net (code "20") (name "MOSI") (class "Default")
      (node (ref "J1") (pin "14") (pinfunction "14_14") (pintype "bidirectional"))
      (node (ref "U1") (pin "P$B13") (pinfunction "P0.03/AIN1_P$B13") (pintype "bidirectional"))
    )
    (net (code "21") (name "N$1") (class "Default")
      (node (ref "C39") (pin "1") (pinfunction "1_1") (pintype "passive"))
      (node (ref "IC1") (pin "B2") (pinfunction "SYS_B2") (pintype "bidirectional"))
    )
    (net (code "22") (name "Net-(ANT1-FEED)") (class "Default")
      (node (ref "ANT1") (pin "1") (pinfunction "FEED_1") (pintype "input"))
      (node (ref "C22") (pin "1") (pinfunction "1_1") (pintype "passive"))
      (node (ref "C4") (pin "1") (pinfunction "1_1") (pintype "passive"))
      (node (ref "L1") (pin "2") (pinfunction "2_2") (pintype "passive"))
    )
    (net (code "23") (name "Net-(D2-K)") (class "Default")
      (node (ref "C2-EP-DR") (pin "1") (pinfunction "1_1") (pintype "passive"))
      (node (ref "D2") (pin "1") (pinfunction "K_1") (pintype "bidirectional"))
      (node (ref "D4") (pin "2") (pinfunction "A_2") (pintype "bidirectional"))
    )
    (net (code "24") (name "Net-(D5-A)") (class "Default")
      (node (ref "C2-EP-DR") (pin "2") (pinfunction "2_2") (pintype "passive"))
      (node (ref "D5") (pin "2") (pinfunction "A_2") (pintype "bidirectional"))
      (node (ref "L5") (pin "1") (pinfunction "1_1") (pintype "passive"))
      (node (ref "Q3") (pin "3") (pinfunction "D_3") (pintype "bidirectional"))
    )
    (net (code "25") (name "Net-(EPD_C1-Pad2)") (class "Default")
      (node (ref "EPD_C1") (pin "2") (pinfunction "2_2") (pintype "passive"))
      (node (ref "J1") (pin "5") (pinfunction "5_5") (pintype "bidirectional"))
    )
    (net (code "26") (name "Net-(EPD_C2-Pad2)") (class "Default")
      (node (ref "EPD_C2") (pin "2") (pinfunction "2_2") (pintype "passive"))
      (node (ref "J1") (pin "4") (pinfunction "4_4") (pintype "bidirectional"))
    )
    (net (code "27") (name "Net-(EPD_C6-Pad2)") (class "Default")
      (node (ref "EPD_C6") (pin "2") (pinfunction "2_2") (pintype "passive"))
      (node (ref "J1") (pin "18") (pinfunction "18_18") (pintype "bidirectional"))
    )
    (net (code "28") (name "Net-(EPD_C7-Pad2)") (class "Default")
      (node (ref "EPD_C7") (pin "2") (pinfunction "2_2") (pintype "passive"))
      (node (ref "J1") (pin "19") (pinfunction "19_19") (pintype "bidirectional"))
    )
    (net (code "29") (name "Net-(EPD_C8-Pad2)") (class "Default")
      (node (ref "EPD_C8") (pin "2") (pinfunction "2_2") (pintype "passive"))
      (node (ref "J1") (pin "20") (pinfunction "20_20") (pintype "bidirectional"))
    )
    (net (code "30") (name "Net-(EPD_C10-Pad2)") (class "Default")
      (node (ref "EPD_C10") (pin "2") (pinfunction "2_2") (pintype "passive"))
      (node (ref "J1") (pin "22") (pinfunction "22_22") (pintype "bidirectional"))
    )
    (net (code "31") (name "Net-(EPD_C12-Pad2)") (class "Default")
      (node (ref "EPD_C12") (pin "2") (pinfunction "2_2") (pintype "passive"))
      (node (ref "J1") (pin "24") (pinfunction "24_24") (pintype "bidirectional"))
    )
    (net (code "32") (name "Net-(IC1-TS{slash}MR)") (class "Default")
      (node (ref "IC1") (pin "D1") (pinfunction "TS/MR_D1") (pintype "bidirectional"))
      (node (ref "R9") (pin "2") (pinfunction "2_2") (pintype "bidirectional"))
    )
    (net (code "33") (name "Net-(IC2-REG)") (class "Default")
      (node (ref "C32") (pin "1") (pinfunction "1_1") (pintype "passive"))
      (node (ref "IC2") (pin "A2") (pinfunction "REG_A2") (pintype "bidirectional"))
    )
    (net (code "34") (name "Net-(IC3-SDO)") (class "Default")
      (node (ref "IC3") (pin "1") (pinfunction "SDO_1") (pintype "bidirectional"))
      (node (ref "R3") (pin "2") (pinfunction "2_2") (pintype "bidirectional"))
    )
    (net (code "35") (name "Net-(IC9-SCL)") (class "Default")
      (node (ref "IC9") (pin "D1") (pinfunction "SCL_D1") (pintype "bidirectional"))
      (node (ref "R4") (pin "2") (pinfunction "2_2") (pintype "bidirectional"))
    )
    (net (code "36") (name "Net-(IC9-SDA)") (class "Default")
      (node (ref "IC9") (pin "E1") (pinfunction "SDA_E1") (pintype "bidirectional"))
      (node (ref "R2") (pin "2") (pinfunction "2_2") (pintype "bidirectional"))
    )
    (net (code "37") (name "Net-(J4-CC1)") (class "Default")
      (node (ref "J4") (pin "A5") (pinfunction "CC1_A5") (pintype "bidirectional"))
      (node (ref "R1_USB") (pin "2") (pinfunction "2_2") (pintype "bidirectional"))
    )
    (net (code "38") (name "Net-(J4-CC2)") (class "Default")
      (node (ref "J4") (pin "B5") (pinfunction "CC2_B5") (pintype "bidirectional"))
      (node (ref "R2_USB") (pin "1") (pinfunction "1_1") (pintype "bidirectional"))
    )
    (net (code "39") (name "Net-(L2-Pad2)") (class "Default")
      (node (ref "L2") (pin "2") (pinfunction "2_2") (pintype "passive"))
      (node (ref "L3") (pin "1") (pinfunction "1_1") (pintype "passive"))
    )
    (net (code "40") (name "Net-(R1-EP-DR-Pad1)") (class "Default")
      (node (ref "R1-EP-DR") (pin "1") (pinfunction "1_1") (pintype "bidirectional"))
      (node (ref "R_TYPE_SEL") (pin "2") (pinfunction "2_2") (pintype "bidirectional"))
      (node (ref "SJ1") (pin "2") (pinfunction "2_2") (pintype "passive"))
    )
    (net (code "41") (name "Net-(U1-ANT)") (class "Default")
      (node (ref "C3") (pin "1") (pinfunction "1_1") (pintype "passive"))
      (node (ref "L1") (pin "1") (pinfunction "1_1") (pintype "passive"))
      (node (ref "U1") (pin "P$H23") (pinfunction "ANT_P$H23") (pintype "bidirectional"))
    )
    (net (code "42") (name "Net-(U1-DCC)") (class "Default")
      (node (ref "L2") (pin "1") (pinfunction "1_1") (pintype "passive"))
      (node (ref "U1") (pin "P$B3") (pinfunction "DCC_P$B3") (pintype "output"))
    )
    (net (code "43") (name "Net-(U1-DEC1)") (class "Default")
      (node (ref "C5") (pin "1") (pinfunction "1_1") (pintype "passive"))
      (node (ref "U1") (pin "P$C1") (pinfunction "DEC1_P$C1") (pintype "power_in"))
    )
    (net (code "44") (name "Net-(U1-DEC2)") (class "Default")
      (node (ref "C13") (pin "1") (pinfunction "1_1") (pintype "passive"))
      (node (ref "U1") (pin "P$A18") (pinfunction "DEC2_P$A18") (pintype "bidirectional"))
    )
    (net (code "45") (name "Net-(U1-DEC3)") (class "Default")
      (node (ref "C11") (pin "1") (pinfunction "1_1") (pintype "passive"))
      (node (ref "U1") (pin "P$D23") (pinfunction "DEC3_P$D23") (pintype "bidirectional"))
    )
    (net (code "46") (name "Net-(U1-DEC3V3)") (class "Default")
      (node (ref "C20") (pin "1") (pinfunction "1_1") (pintype "passive"))
      (node (ref "U1") (pin "P$AC5") (pinfunction "DEC3V3_P$AC5") (pintype "bidirectional"))
    )
    (net (code "47") (name "Net-(U1-DEC4)") (class "Default")
      (node (ref "C10") (pin "1") (pinfunction "1_1") (pintype "passive"))
      (node (ref "C15") (pin "1") (pinfunction "1_1") (pintype "passive"))
      (node (ref "C16") (pin "1") (pinfunction "1_1") (pintype "passive"))
      (node (ref "L3") (pin "2") (pinfunction "2_2") (pintype "passive"))
      (node (ref "U1") (pin "P$B5") (pinfunction "DEC4_P$B5") (pintype "power_in"))
      (node (ref "U1") (pin "P$E24") (pinfunction "DEC6_P$E24") (pintype "bidirectional"))
    )
    (net (code "48") (name "Net-(U1-DEC5)") (class "Default")
      (node (ref "C9") (pin "1") (pinfunction "1_1") (pintype "passive"))
      (node (ref "U1") (pin "P$N24") (pinfunction "DEC5_P$N24") (pintype "bidirectional"))
    )
    (net (code "49") (name "Net-(U1-P0.00{slash}XL1)") (class "Default")
      (node (ref "C17") (pin "2") (pinfunction "2_2") (pintype "passive"))
      (node (ref "U1") (pin "P$D2") (pinfunction "P0.00/XL1_P$D2") (pintype "bidirectional"))
      (node (ref "X2") (pin "1") (pinfunction "1_1") (pintype "passive"))
    )
    (net (code "50") (name "Net-(U1-P0.01{slash}XL2)") (class "Default")
      (node (ref "C18") (pin "2") (pinfunction "2_2") (pintype "passive"))
      (node (ref "U1") (pin "P$F2") (pinfunction "P0.01/XL2_P$F2") (pintype "bidirectional"))
      (node (ref "X2") (pin "2") (pinfunction "2_2") (pintype "passive"))
    )
    (net (code "51") (name "Net-(U1-XC1)") (class "Default")
      (node (ref "C1") (pin "1") (pinfunction "1_1") (pintype "passive"))
      (node (ref "U1") (pin "P$B24") (pinfunction "XC1_P$B24") (pintype "input"))
      (node (ref "X1") (pin "1") (pinfunction "1_1") (pintype "passive"))
    )
    (net (code "52") (name "Net-(U1-XC2)") (class "Default")
      (node (ref "C2") (pin "1") (pinfunction "1_1") (pintype "passive"))
      (node (ref "U1") (pin "P$A23") (pinfunction "XC2_P$A23") (pintype "output"))
      (node (ref "X1") (pin "3") (pinfunction "3_3") (pintype "passive"))
    )
    (net (code "53") (name "OUT+") (class "Default")
      (node (ref "IC2") (pin "A3") (pinfunction "OUT+_A3") (pintype "bidirectional"))
      (node (ref "TP_OP") (pin "TP") (pinfunction "TP_TP") (pintype "input"))
    )
    (net (code "54") (name "OUT-") (class "Default")
      (node (ref "IC2") (pin "C3") (pinfunction "OUT-_C3") (pintype "bidirectional"))
      (node (ref "TP_ON") (pin "TP") (pinfunction "TP_TP") (pintype "input"))
    )
    (net (code "55") (name "P0.04") (class "Default")
      (node (ref "U1") (pin "P$J1") (pinfunction "P0.04/AIN2_P$J1") (pintype "bidirectional"))
    )
    (net (code "56") (name "P0.09") (class "Default")
      (node (ref "U1") (pin "P$L24") (pinfunction "P0.09/NFC1_P$L24") (pintype "bidirectional"))
    )
    (net (code "57") (name "P0.13") (class "Default")
      (node (ref "C30") (pin "1") (pinfunction "1_1") (pintype "passive"))
      (node (ref "R5") (pin "1") (pinfunction "1_1") (pintype "bidirectional"))
      (node (ref "SW_UP") (pin "2") (pinfunction "2_2") (pintype "passive"))
      (node (ref "U1") (pin "P$AD8") (pinfunction "P0.13_P$AD8") (pintype "bidirectional"))
    )
    (net (code "58") (name "P0.14") (class "Default")
      (node (ref "C31") (pin "1") (pinfunction "1_1") (pintype "passive"))
      (node (ref "R8") (pin "1") (pinfunction "1_1") (pintype "bidirectional"))
      (node (ref "SW_NET") (pin "2") (pinfunction "2_2") (pintype "passive"))
      (node (ref "U1") (pin "P$AC9") (pinfunction "P0.14_P$AC9") (pintype "bidirectional"))
    )
    (net (code "59") (name "P0.19") (class "Default")
      (node (ref "U1") (pin "P$AC15") (pinfunction "P0.19_P$AC15") (pintype "bidirectional"))
    )
    (net (code "60") (name "P0.20") (class "Default")
      (node (ref "U1") (pin "P$AD16") (pinfunction "P0.20_P$AD16") (pintype "bidirectional"))
    )
    (net (code "61") (name "P0.21") (class "Default")
      (node (ref "U1") (pin "P$AC17") (pinfunction "P0.21_P$AC17") (pintype "bidirectional"))
    )
    (net (code "62") (name "P0.22") (class "Default")
      (node (ref "U1") (pin "P$AD18") (pinfunction "P0.22_P$AD18") (pintype "bidirectional"))
    )
    (net (code "63") (name "P0.23") (class "Default")
      (node (ref "U1") (pin "P$AC19") (pinfunction "P0.23_P$AC19") (pintype "bidirectional"))
    )
    (net (code "64") (name "P0.24") (class "Default")
      (node (ref "U1") (pin "P$AD20") (pinfunction "P0.24_P$AD20") (pintype "bidirectional"))
    )
    (net (code "65") (name "P0.25") (class "Default")
      (node (ref "U1") (pin "P$AC21") (pinfunction "P0.25_P$AC21") (pintype "bidirectional"))
    )
    (net (code "66") (name "P0.26") (class "Default")
      (node (ref "U1") (pin "P$G1") (pinfunction "P0.26_P$G1") (pintype "bidirectional"))
    )
    (net (code "67") (name "P0.27") (class "Default")
      (node (ref "U1") (pin "P$H2") (pinfunction "P0.27_P$H2") (pintype "bidirectional"))
    )
    (net (code "68") (name "P0.28") (class "Default")
      (node (ref "U1") (pin "P$B11") (pinfunction "P0.28/AIN4_P$B11") (pintype "bidirectional"))
    )
    (net (code "69") (name "P0.29") (class "Default")
      (node (ref "U1") (pin "P$A10") (pinfunction "P0.29/AIN5_P$A10") (pintype "bidirectional"))
    )
    (net (code "70") (name "P0.30") (class "Default")
      (node (ref "U1") (pin "P$B9") (pinfunction "P0.30/AIN6_P$B9") (pintype "bidirectional"))
    )
    (net (code "71") (name "P0.31") (class "Default")
      (node (ref "U1") (pin "P$A8") (pinfunction "P0.31/AIN7_P$A8") (pintype "bidirectional"))
    )
    (net (code "72") (name "P1.01") (class "Default")
      (node (ref "Q1") (pin "1") (pinfunction "G_1") (pintype "bidirectional"))
      (node (ref "R_PWR_EPD") (pin "1") (pinfunction "1_1") (pintype "bidirectional"))
      (node (ref "U1") (pin "P$Y23") (pinfunction "P1.01_P$Y23") (pintype "bidirectional"))
    )
    (net (code "73") (name "P1.02") (class "Default")
      (node (ref "C29") (pin "1") (pinfunction "1_1") (pintype "passive"))
      (node (ref "R7") (pin "1") (pinfunction "1_1") (pintype "bidirectional"))
      (node (ref "SW_DN") (pin "2") (pinfunction "2_2") (pintype "passive"))
      (node (ref "U1") (pin "P$W24") (pinfunction "P1.02_P$W24") (pintype "bidirectional"))
    )
    (net (code "74") (name "P1.03") (class "Default")
      (node (ref "U1") (pin "P$V23") (pinfunction "P1.03_P$V23") (pintype "bidirectional"))
    )
    (net (code "75") (name "P1.04") (class "Default")
      (node (ref "U1") (pin "P$U24") (pinfunction "P1.04_P$U24") (pintype "bidirectional"))
    )
    (net (code "76") (name "P1.05") (class "Default")
      (node (ref "U1") (pin "P$T23") (pinfunction "P1.05_P$T23") (pintype "bidirectional"))
    )
    (net (code "77") (name "P1.06") (class "Default")
      (node (ref "U1") (pin "P$R24") (pinfunction "P1.06_P$R24") (pintype "bidirectional"))
    )
    (net (code "78") (name "P1.07") (class "Default")
      (node (ref "U1") (pin "P$P23") (pinfunction "P1.07_P$P23") (pintype "bidirectional"))
    )
    (net (code "79") (name "P1.09") (class "Default")
      (node (ref "U1") (pin "P$R1") (pinfunction "P1.09_P$R1") (pintype "bidirectional"))
    )
    (net (code "80") (name "P1.10") (class "Default")
      (node (ref "U1") (pin "P$A20") (pinfunction "P1.10_P$A20") (pintype "bidirectional"))
    )
    (net (code "81") (name "P1.11") (class "Default")
      (node (ref "U1") (pin "P$B19") (pinfunction "P1.11_P$B19") (pintype "bidirectional"))
    )
    (net (code "82") (name "P1.12") (class "Default")
      (node (ref "U1") (pin "P$B17") (pinfunction "P1.12_P$B17") (pintype "bidirectional"))
    )
    (net (code "83") (name "P1.13") (class "Default")
      (node (ref "U1") (pin "P$A16") (pinfunction "P1.13_P$A16") (pintype "bidirectional"))
    )
    (net (code "84") (name "P1.14") (class "Default")
      (node (ref "U1") (pin "P$B15") (pinfunction "P1.14_P$B15") (pintype "bidirectional"))
    )
    (net (code "85") (name "P1.15") (class "Default")
      (node (ref "U1") (pin "P$A14") (pinfunction "P1.15_P$A14") (pintype "bidirectional"))
    )
    (net (code "86") (name "PMIC_INT") (class "Default")
      (node (ref "IC1") (pin "A1") (pinfunction "~{INT}_A1") (pintype "bidirectional"))
      (node (ref "U1") (pin "P$T2") (pinfunction "P0.11_P$T2") (pintype "bidirectional"))
    )
    (net (code "87") (name "PREVGH") (class "Default")
      (node (ref "D5") (pin "1") (pinfunction "K_1") (pintype "bidirectional"))
      (node (ref "EPD_C9") (pin "2") (pinfunction "2_2") (pintype "passive"))
      (node (ref "J1") (pin "21") (pinfunction "21_21") (pintype "bidirectional"))
    )
    (net (code "88") (name "PREVGL") (class "Default")
      (node (ref "D2") (pin "2") (pinfunction "A_2") (pintype "bidirectional"))
      (node (ref "EPD_C11") (pin "2") (pinfunction "2_2") (pintype "passive"))
      (node (ref "J1") (pin "23") (pinfunction "23_23") (pintype "bidirectional"))
    )
    (net (code "89") (name "RESE") (class "Default")
      (node (ref "J1") (pin "3") (pinfunction "3_3") (pintype "bidirectional"))
      (node (ref "Q3") (pin "2") (pinfunction "S_2") (pintype "bidirectional"))
      (node (ref "R1-EP-DR") (pin "2") (pinfunction "2_2") (pintype "bidirectional"))
    )
    (net (code "90") (name "RESET") (class "Default")
      (node (ref "J2") (pin "6") (pinfunction "6_6") (pintype "bidirectional"))
      (node (ref "TP_RESET") (pin "TP") (pinfunction "TP_TP") (pintype "input"))
      (node (ref "U1") (pin "P$AC13") (pinfunction "P0.18/RESET_P$AC13") (pintype "bidirectional"))
    )
    (net (code "91") (name "SCK") (class "Default")
      (node (ref "J1") (pin "13") (pinfunction "13_13") (pintype "bidirectional"))
      (node (ref "U1") (pin "P$A12") (pinfunction "P0.02/AIN0_P$A12") (pintype "bidirectional"))
    )
    (net (code "92") (name "SCL") (class "Default")
      (node (ref "IC1") (pin "B1") (pinfunction "SCL_B1") (pintype "bidirectional"))
      (node (ref "IC2") (pin "C1") (pinfunction "SCL_C1") (pintype "bidirectional"))
      (node (ref "IC3") (pin "12") (pinfunction "SCX_12") (pintype "bidirectional"))
      (node (ref "R17") (pin "2") (pinfunction "2_2") (pintype "bidirectional"))
      (node (ref "R4") (pin "1") (pinfunction "1_1") (pintype "bidirectional"))
      (node (ref "TP_SCL") (pin "TP") (pinfunction "TP_TP") (pintype "input"))
      (node (ref "U1") (pin "P$M2") (pinfunction "P0.07_P$M2") (pintype "bidirectional"))
      (node (ref "U3") (pin "7") (pinfunction "SCL_7") (pintype "input"))
    )
    (net (code "93") (name "SDA") (class "Default")
      (node (ref "IC1") (pin "C1") (pinfunction "SDA_C1") (pintype "bidirectional"))
      (node (ref "IC2") (pin "B2") (pinfunction "SDA_B2") (pintype "bidirectional"))
      (node (ref "IC3") (pin "2") (pinfunction "SDX_2") (pintype "bidirectional"))
      (node (ref "R18") (pin "2") (pinfunction "2_2") (pintype "bidirectional"))
      (node (ref "R2") (pin "1") (pinfunction "1_1") (pintype "bidirectional"))
      (node (ref "TP_SDA") (pin "TP") (pinfunction "TP_TP") (pintype "input"))
      (node (ref "U1") (pin "P$L1") (pinfunction "P0.06_P$L1") (pintype "bidirectional"))
      (node (ref "U3") (pin "8") (pinfunction "SDA_8") (pintype "bidirectional"))
    )
    (net (code "94") (name "SWDCLK") (class "Default")
      (node (ref "J2") (pin "4") (pinfunction "4_4") (pintype "bidirectional"))
      (node (ref "TP_SWDCLK") (pin "TP") (pinfunction "TP_TP") (pintype "input"))
      (node (ref "U1") (pin "P$AA24") (pinfunction "SWDCLK_P$AA24") (pintype "input"))
    )
    (net (code "95") (name "SWDIO") (class "Default")
      (node (ref "J2") (pin "2") (pinfunction "2_2") (pintype "bidirectional"))
      (node (ref "TP_SWDIO") (pin "TP") (pinfunction "TP_TP") (pintype "input"))
      (node (ref "U1") (pin "P$AC24") (pinfunction "SWDIO_P$AC24") (pintype "bidirectional"))
    )
    (net (code "96") (name "SWO") (class "Default")
      (node (ref "TP_SWO") (pin "TP") (pinfunction "TP_TP") (pintype "input"))
      (node (ref "U1") (pin "P$AD22") (pinfunction "P1.00_P$AD22") (pintype "bidirectional"))
    )
    (net (code "97") (name "VBAT") (class "Default")
      (node (ref "C27") (pin "2") (pinfunction "2_2") (pintype "passive"))
      (node (ref "C37") (pin "1") (pinfunction "1_1") (pintype "passive"))
      (node (ref "IC1") (pin "C2") (pinfunction "BAT_C2") (pintype "bidirectional"))
      (node (ref "TP_VBAT") (pin "TP") (pinfunction "TP_TP") (pintype "input"))
      (node (ref "U3") (pin "2") (pinfunction "CELL_2") (pintype "power_in"))
      (node (ref "U3") (pin "3") (pinfunction "VDD_3") (pintype "power_in"))
    )
    (net (code "98") (name "VBUS") (class "Default")
      (node (ref "C21") (pin "1") (pinfunction "1_1") (pintype "passive"))
      (node (ref "C38") (pin "2") (pinfunction "2_2") (pintype "passive"))
      (node (ref "C42") (pin "1") (pinfunction "1_1") (pintype "passive"))
      (node (ref "C43") (pin "1") (pinfunction "1_1") (pintype "passive"))
      (node (ref "D3") (pin "5") (pinfunction "VBUS_5") (pintype "bidirectional"))
      (node (ref "IC1") (pin "A2") (pinfunction "IN_A2") (pintype "bidirectional"))
      (node (ref "J4") (pin "A4_B9") (pinfunction "VBUS_A4_B9") (pintype "power_in"))
      (node (ref "J4") (pin "A9_B4") (pinfunction "VBUS_A9_B4") (pintype "power_in"))
      (node (ref "U1") (pin "P$AD2") (pinfunction "VBUS_P$AD2") (pintype "power_in"))
    )
    (net (code "99") (name "VREG") (class "Default")
      (node (ref "C23") (pin "2") (pinfunction "2_2") (pintype "passive"))
      (node (ref "C24") (pin "2") (pinfunction "2_2") (pintype "passive"))
      (node (ref "IC9") (pin "A1") (pinfunction "EN_A1") (pintype "bidirectional"))
      (node (ref "IC9") (pin "A2") (pinfunction "VIN_1_A2") (pintype "bidirectional"))
      (node (ref "IC9") (pin "A3") (pinfunction "VIN_2_A3") (pintype "bidirectional"))
      (node (ref "TP_VREG") (pin "TP") (pinfunction "TP_TP") (pintype "input"))
    )
    (net (code "100") (name "unconnected-(ANT1-NC-Pad2)") (class "Default")
      (node (ref "ANT1") (pin "2") (pinfunction "NC_2") (pintype "no_connect"))
    )
    (net (code "101") (name "unconnected-(IC3-ASCL-Pad11)") (class "Default")
      (node (ref "IC3") (pin "11") (pinfunction "ASCL_11") (pintype "bidirectional"))
    )
    (net (code "102") (name "unconnected-(IC3-ASDA-Pad4)") (class "Default")
      (node (ref "IC3") (pin "4") (pinfunction "ASDA_4") (pintype "bidirectional"))
    )
    (net (code "103") (name "unconnected-(J1-Pad1)") (class "Default")
      (node (ref "J1") (pin "1") (pinfunction "1_1") (pintype "bidirectional"))
    )
    (net (code "104") (name "unconnected-(J1-Pad6)") (class "Default")
      (node (ref "J1") (pin "6") (pinfunction "6_6") (pintype "bidirectional"))
    )
    (net (code "105") (name "unconnected-(J1-Pad7)") (class "Default")
      (node (ref "J1") (pin "7") (pinfunction "7_7") (pintype "bidirectional"))
    )
    (net (code "106") (name "unconnected-(J4-SBU1-PadA8)") (class "Default")
      (node (ref "J4") (pin "A8") (pinfunction "SBU1_A8") (pintype "bidirectional"))
    )
    (net (code "107") (name "unconnected-(J4-SBU2-PadB8)") (class "Default")
      (node (ref "J4") (pin "B8") (pinfunction "SBU2_B8") (pintype "bidirectional"))
    )
    (net (code "108") (name "unconnected-(U1-DCCH-PadP$AB2)") (class "Default")
      (node (ref "U1") (pin "P$AB2") (pinfunction "DCCH_P$AB2") (pintype "bidirectional"))
    )
  )
)
